# AirMeter_io_Sensor_Assembly_v1_0.net
KiCad netlist of a schematic drawn in EasyEDA
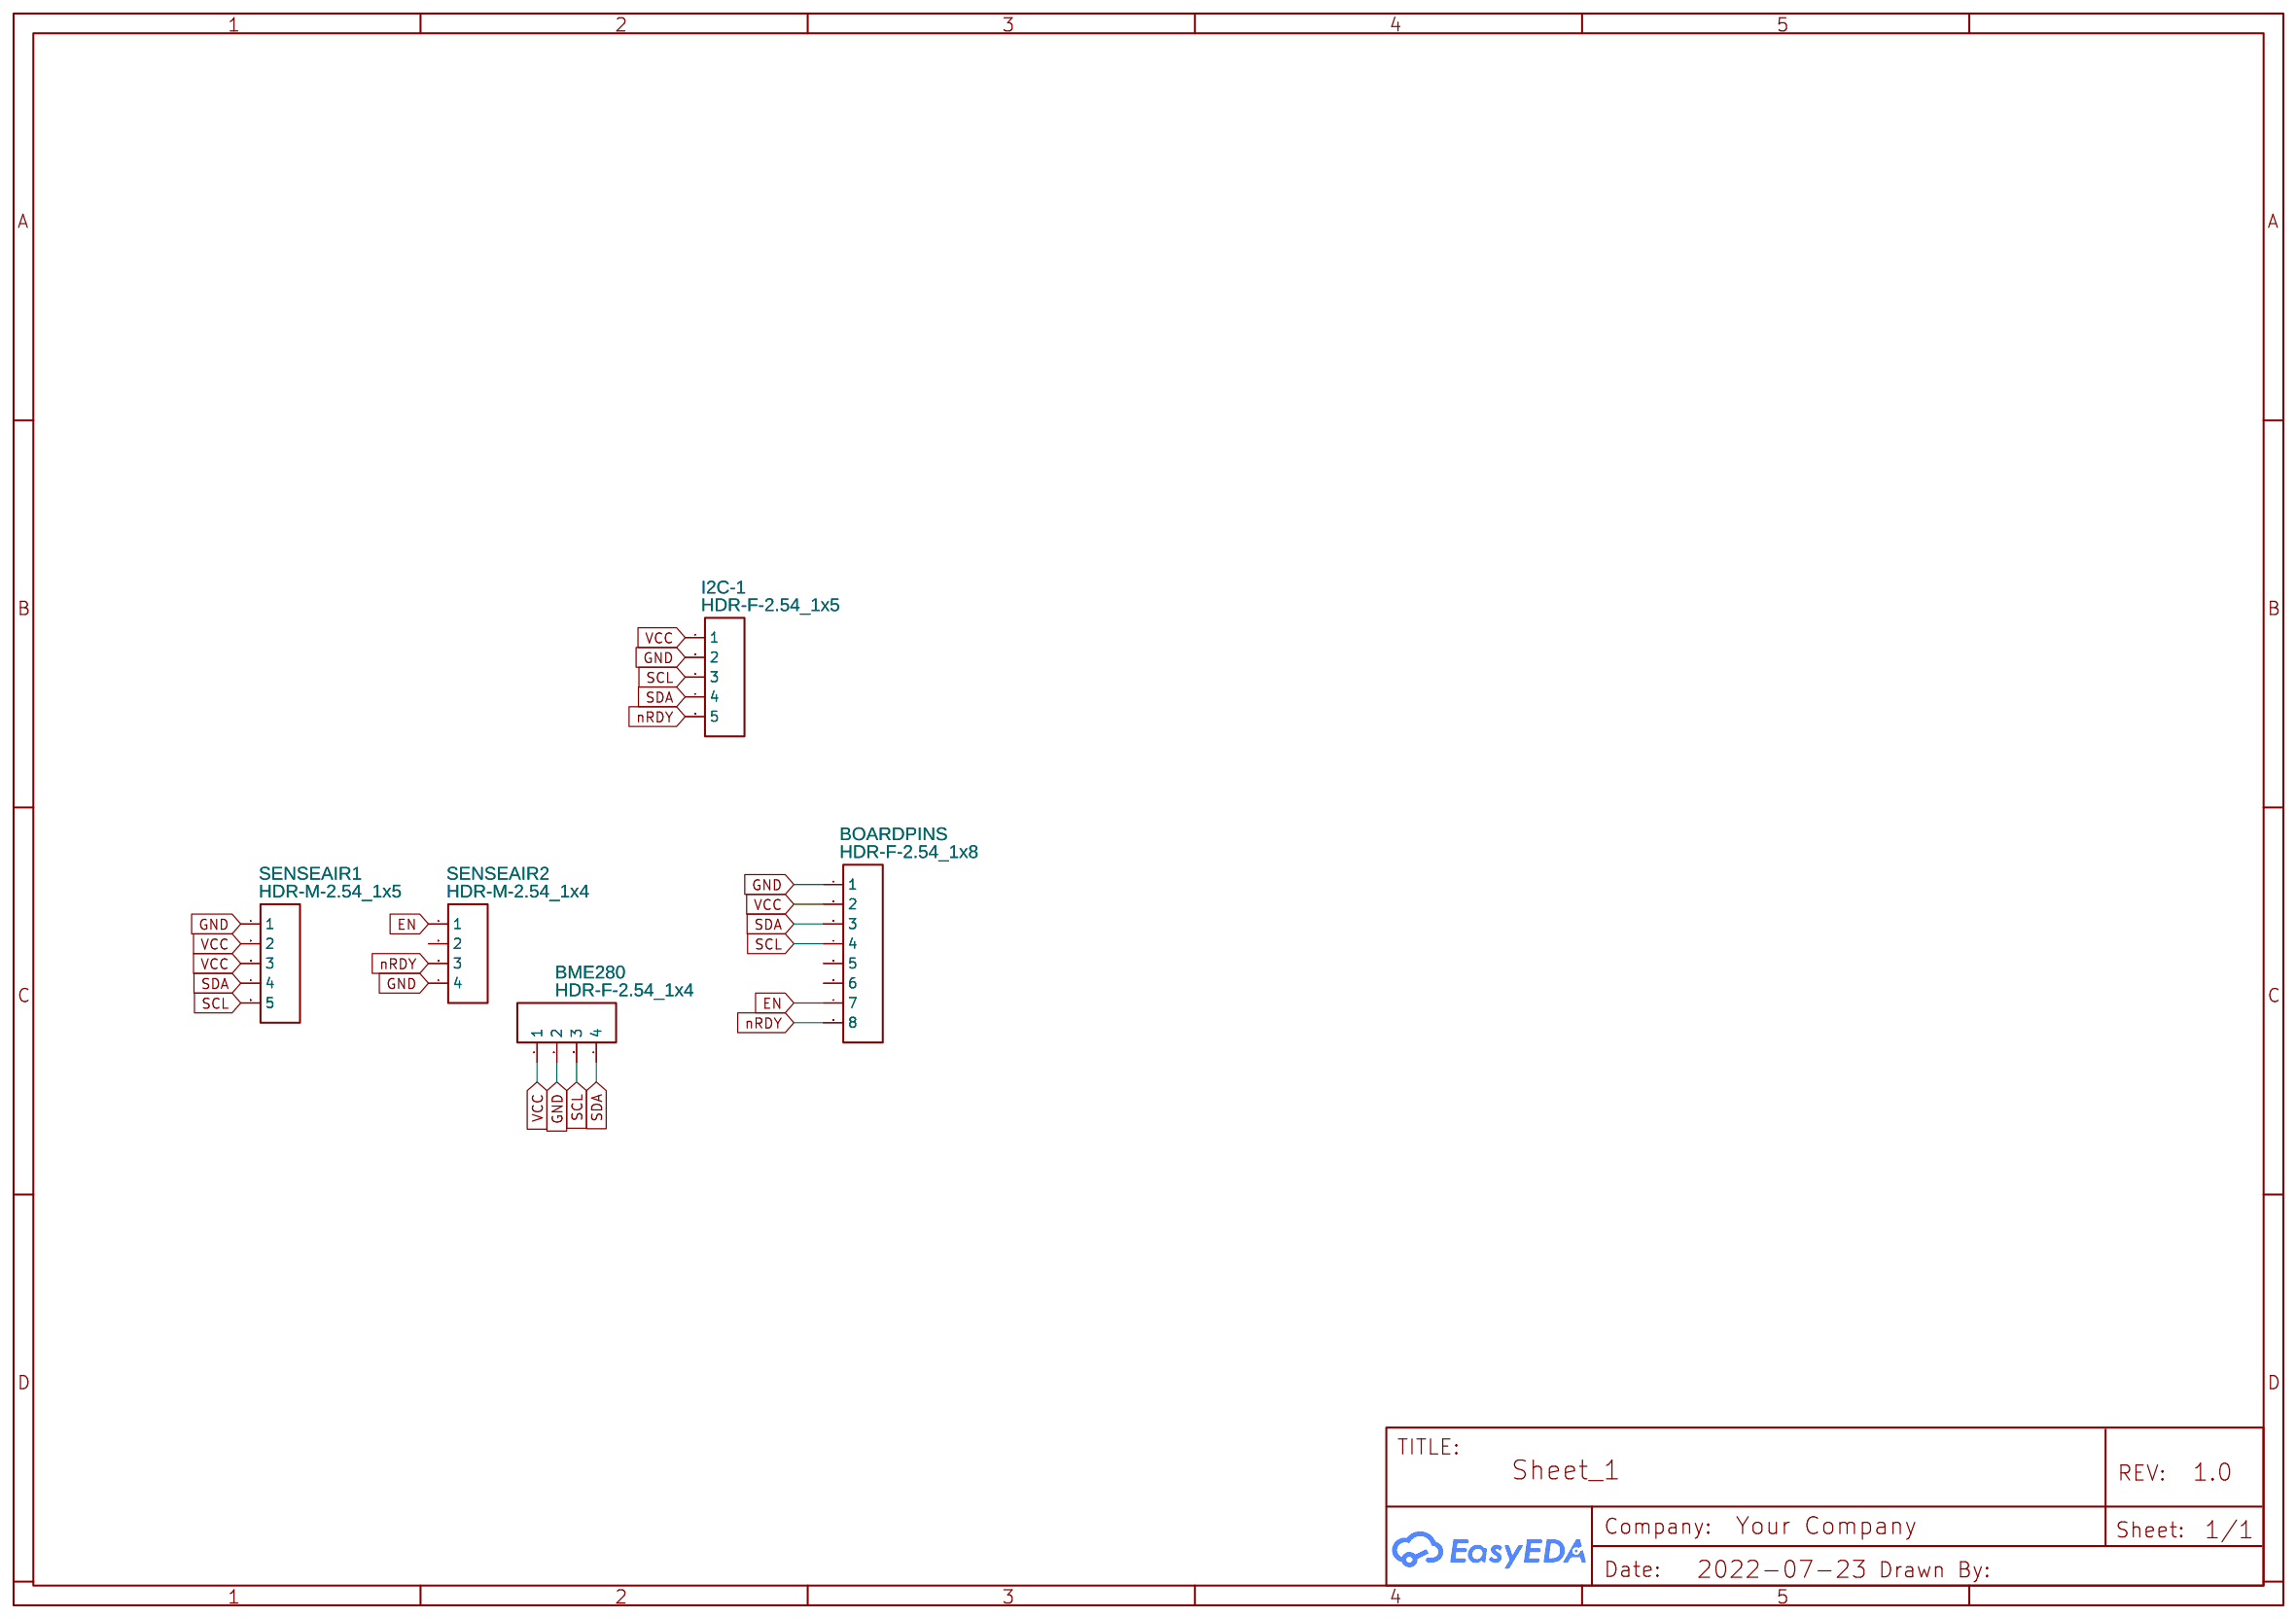
[diagram p0: schematic sheet]

(export (version "E")
  (design (tool "Eeschema 10.0.6"))
  (components
    (comp (ref "BME280")
      (value "HDR-F-2.54_1x4")
      (fields (field (name "BOM_Supplier Part") "C225501"))
      (libsource (lib "") (part "HDR-F-2.54_1x4"))
    )
    (comp (ref "BOARDPINS")
      (value "HDR-F-2.54_1x8")
      (fields (field (name "BOM_Supplier Part") "C225505"))
      (libsource (lib "") (part "HDR-F-2.54_1x8"))
    )
    (comp (ref "I2C-1")
      (value "HDR-F-2.54_1x5")
      (fields (field (name "BOM_Supplier Part") "C50950"))
      (libsource (lib "") (part "HDR-F-2.54_1x5"))
    )
    (comp (ref "SENSEAIR1")
      (value "HDR-M-2.54_1x5")
      (fields (field (name "BOM_Supplier Part") "C358687"))
      (libsource (lib "") (part "HDR-M-2.54_1x5"))
    )
    (comp (ref "SENSEAIR2")
      (value "HDR-M-2.54_1x4")
      (fields (field (name "BOM_Supplier Part") "C124378"))
      (libsource (lib "") (part "HDR-M-2.54_1x4"))
    )
  )
  (nets
    (net (code "1") (name "EN") (class "Default")
      (node (ref "BOARDPINS") (pin "7") (pinfunction "7_7") (pintype "unspecified"))
      (node (ref "SENSEAIR2") (pin "1") (pinfunction "1_1") (pintype "unspecified"))
    )
    (net (code "2") (name "GND") (class "Default")
      (node (ref "BME280") (pin "2") (pinfunction "2_2") (pintype "unspecified"))
      (node (ref "BOARDPINS") (pin "1") (pinfunction "1_1") (pintype "unspecified"))
      (node (ref "I2C-1") (pin "2") (pinfunction "2_2") (pintype "unspecified"))
      (node (ref "SENSEAIR1") (pin "1") (pinfunction "1_1") (pintype "unspecified"))
      (node (ref "SENSEAIR2") (pin "4") (pinfunction "4_4") (pintype "unspecified"))
    )
    (net (code "3") (name "SCL") (class "Default")
      (node (ref "BME280") (pin "3") (pinfunction "3_3") (pintype "unspecified"))
      (node (ref "BOARDPINS") (pin "4") (pinfunction "4_4") (pintype "unspecified"))
      (node (ref "I2C-1") (pin "3") (pinfunction "3_3") (pintype "unspecified"))
      (node (ref "SENSEAIR1") (pin "5") (pinfunction "5_5") (pintype "unspecified"))
    )
    (net (code "4") (name "SDA") (class "Default")
      (node (ref "BME280") (pin "4") (pinfunction "4_4") (pintype "unspecified"))
      (node (ref "BOARDPINS") (pin "3") (pinfunction "3_3") (pintype "unspecified"))
      (node (ref "I2C-1") (pin "4") (pinfunction "4_4") (pintype "unspecified"))
      (node (ref "SENSEAIR1") (pin "4") (pinfunction "4_4") (pintype "unspecified"))
    )
    (net (code "5") (name "VCC") (class "Default")
      (node (ref "BME280") (pin "1") (pinfunction "1_1") (pintype "unspecified"))
      (node (ref "BOARDPINS") (pin "2") (pinfunction "2_2") (pintype "unspecified"))
      (node (ref "I2C-1") (pin "1") (pinfunction "1_1") (pintype "unspecified"))
      (node (ref "SENSEAIR1") (pin "2") (pinfunction "2_2") (pintype "unspecified"))
      (node (ref "SENSEAIR1") (pin "3") (pinfunction "3_3") (pintype "unspecified"))
    )
    (net (code "6") (name "nRDY") (class "Default")
      (node (ref "BOARDPINS") (pin "8") (pinfunction "8_8") (pintype "unspecified"))
      (node (ref "I2C-1") (pin "5") (pinfunction "5_5") (pintype "unspecified"))
      (node (ref "SENSEAIR2") (pin "3") (pinfunction "3_3") (pintype "unspecified"))
    )
    (net (code "7") (name "unconnected-(BOARDPINS-Pad5)") (class "Default")
      (node (ref "BOARDPINS") (pin "5") (pinfunction "5_5") (pintype "unspecified"))
    )
    (net (code "8") (name "unconnected-(BOARDPINS-Pad6)") (class "Default")
      (node (ref "BOARDPINS") (pin "6") (pinfunction "6_6") (pintype "unspecified"))
    )
    (net (code "9") (name "unconnected-(SENSEAIR2-Pad2)") (class "Default")
      (node (ref "SENSEAIR2") (pin "2") (pinfunction "2_2") (pintype "unspecified"))
    )
  )
)
